# tick-box-1591A-mk-3_0.net
KiCad netlist of a schematic drawn in EAGLE
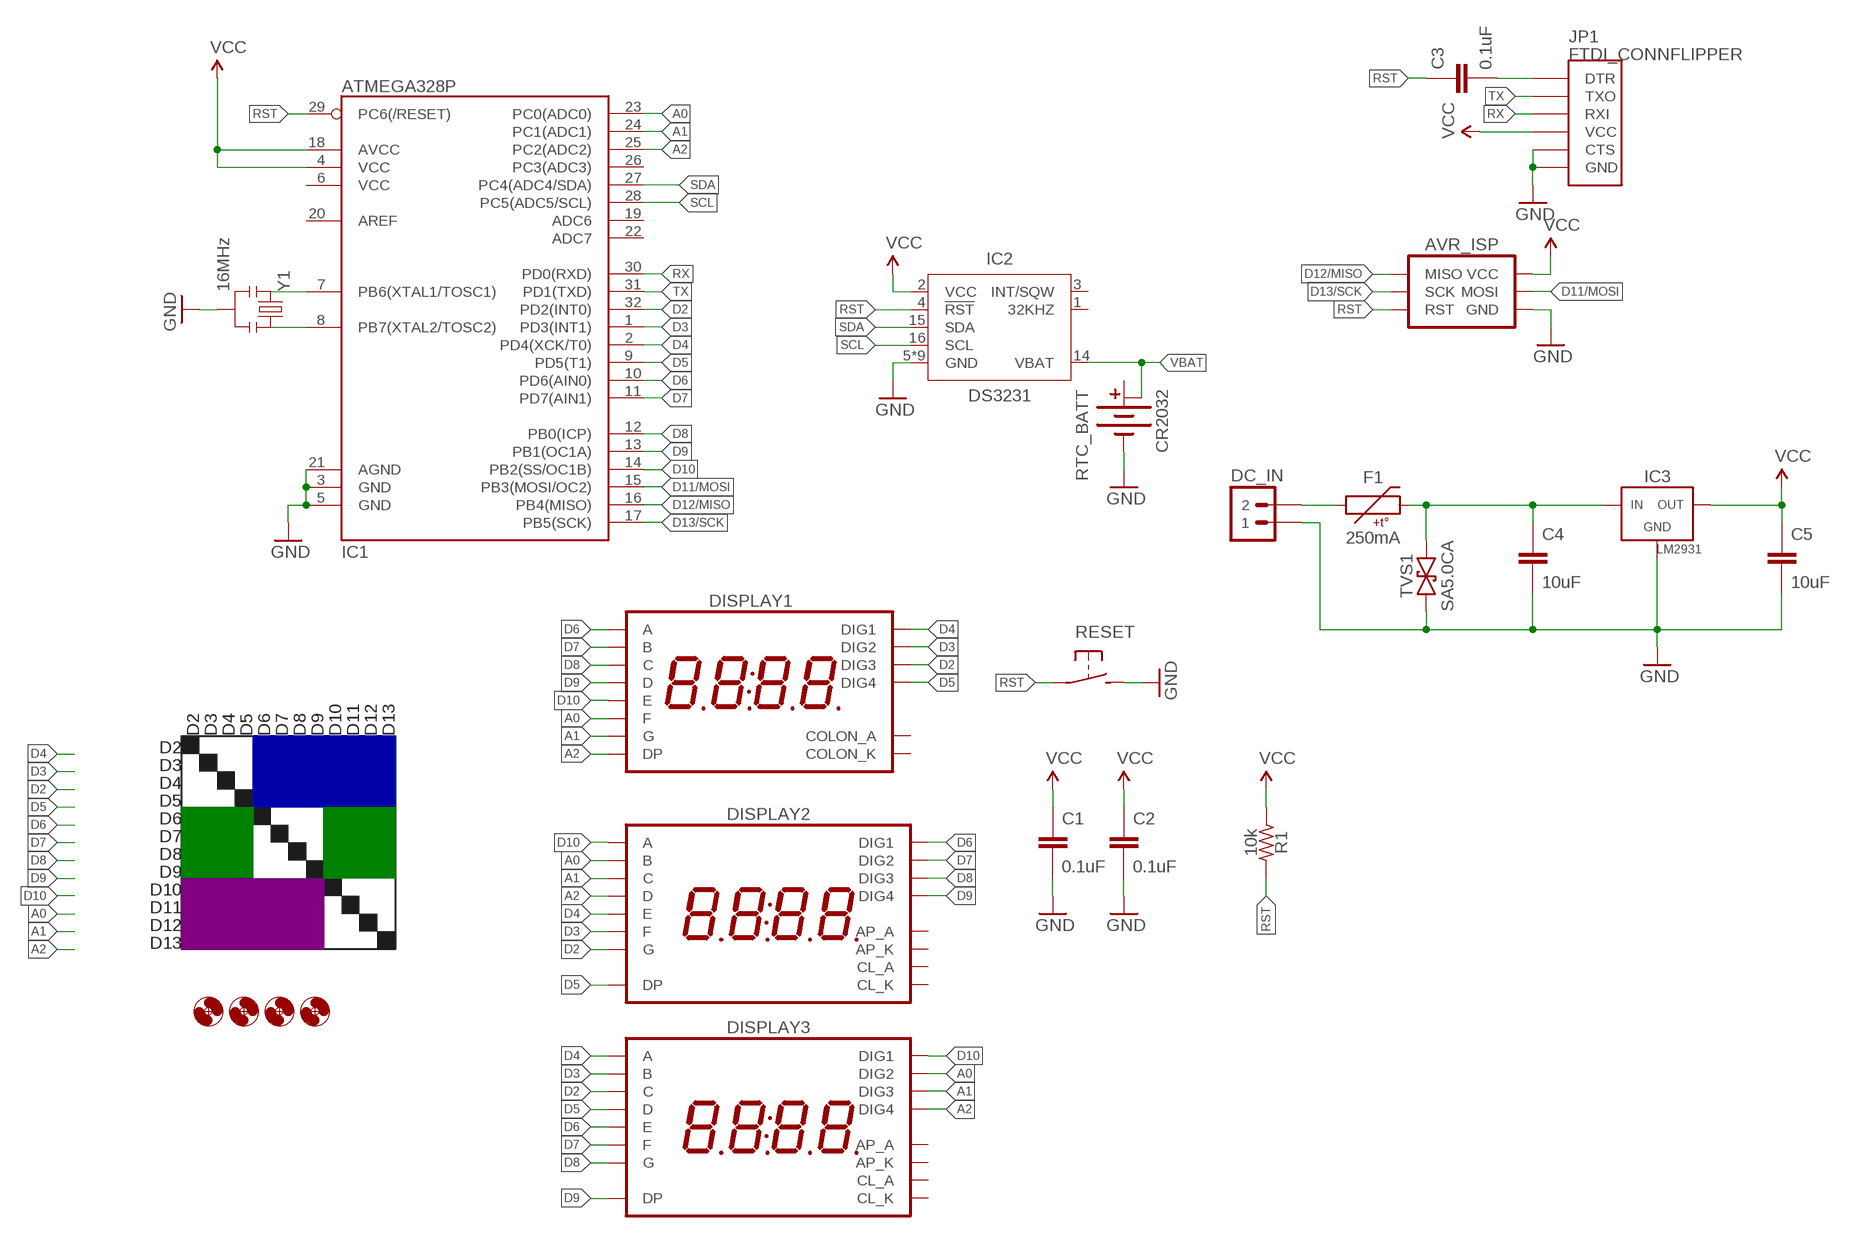
[diagram p0: schematic, sheet 1]

(export (version "E")
  (design (tool "Eeschema 10.0.6"))
  (components
    (comp (ref "AVR_ISP")
      (value "AVR_SPI_PRG_6PTH")
      (footprint "eagle-import:2X3")
      (libsource (lib "eagle-import") (part "AVR_SPI_PRG_6PTH"))
    )
    (comp (ref "C1")
      (value "0.1uF")
      (footprint "eagle-import:C0603")
      (libsource (lib "eagle-import") (part "CAPACITOR-CERAMICC0603"))
    )
    (comp (ref "C2")
      (value "0.1uF")
      (footprint "eagle-import:C0603")
      (libsource (lib "eagle-import") (part "CAPACITOR-CERAMICC0603"))
    )
    (comp (ref "C3")
      (value "0.1uF")
      (footprint "eagle-import:C0603")
      (libsource (lib "eagle-import") (part "CAPACITOR-CERAMICC0603"))
    )
    (comp (ref "C4")
      (value "10uF")
      (footprint "eagle-import:C1206")
      (libsource (lib "eagle-import") (part "CAPACITOR-CERAMICC1206"))
    )
    (comp (ref "C5")
      (value "10uF")
      (footprint "eagle-import:C1206")
      (libsource (lib "eagle-import") (part "CAPACITOR-CERAMICC1206"))
    )
    (comp (ref "DC_IN")
      (value "M02PTH")
      (footprint "eagle-import:1X02")
      (libsource (lib "eagle-import") (part "M02PTH"))
    )
    (comp (ref "DISPLAY1")
      (value "7SEG_4DIGIT_COLON14.2MM-CC-NS")
      (footprint "eagle-import:7SEG_4DIG_NS")
      (libsource (lib "eagle-import") (part "7SEG_4DIGIT_COLON14.2MM-CC-NS"))
    )
    (comp (ref "DISPLAY2")
      (value "7SEG_4DIGIT_COLON_APOS")
      (footprint "eagle-import:7SEG_4DIG_10MM")
      (libsource (lib "eagle-import") (part "7SEG_4DIGIT_COLON_APOS"))
    )
    (comp (ref "DISPLAY3")
      (value "7SEG_4DIGIT_COLON_APOS")
      (footprint "eagle-import:7SEG_4DIG_10MM")
      (libsource (lib "eagle-import") (part "7SEG_4DIGIT_COLON_APOS"))
    )
    (comp (ref "F1")
      (value "250mA")
      (footprint "eagle-import:PTC-1206")
      (libsource (lib "eagle-import") (part "PTCSMD"))
    )
    (comp (ref "H1")
      (value "HOLE#2")
      (footprint "eagle-import:HOLE-#2")
      (libsource (lib "eagle-import") (part "HOLE#2"))
    )
    (comp (ref "H2")
      (value "HOLE#2")
      (footprint "eagle-import:HOLE-#2")
      (libsource (lib "eagle-import") (part "HOLE#2"))
    )
    (comp (ref "H3")
      (value "HOLE#2")
      (footprint "eagle-import:HOLE-#2")
      (libsource (lib "eagle-import") (part "HOLE#2"))
    )
    (comp (ref "H4")
      (value "HOLE#2")
      (footprint "eagle-import:HOLE-#2")
      (libsource (lib "eagle-import") (part "HOLE#2"))
    )
    (comp (ref "IC1")
      (value "ATMEGA328P")
      (footprint "eagle-import:TQFP32-08")
      (libsource (lib "eagle-import") (part "ATMEGA328_SMT"))
    )
    (comp (ref "IC2")
      (value "DS3231")
      (footprint "eagle-import:SO16W")
      (libsource (lib "eagle-import") (part "DS3231"))
    )
    (comp (ref "IC3")
      (value "LM2931")
      (footprint "eagle-import:SO08")
      (libsource (lib "eagle-import") (part "LM2931-FIXED"))
    )
    (comp (ref "JP1")
      (value "FTDI_CONNFLIPPER")
      (footprint "eagle-import:FTDI_CONN_FLIP")
      (libsource (lib "eagle-import") (part "FTDI_CONNFLIPPER"))
    )
    (comp (ref "R1")
      (value "10k")
      (footprint "eagle-import:R0603")
      (libsource (lib "eagle-import") (part "RESISTORR0603"))
    )
    (comp (ref "RESET")
      (value "SPST-NO-TACT3MM-PTH-SMALL-PADS")
      (footprint "eagle-import:DTS-3-SMALL-PADS")
      (libsource (lib "eagle-import") (part "SPST-NO-TACT3MM-PTH-SMALL-PADS"))
    )
    (comp (ref "RTC_BATT")
      (value "CR2032")
      (footprint "eagle-import:BATTCON_20MM_MINE")
      (libsource (lib "eagle-import") (part "BATTERY-COINCR2032_SMD"))
    )
    (comp (ref "TVS1")
      (value "SA5.0CA")
      (footprint "eagle-import:SMA-DIODE-TVS-BIDIR")
      (libsource (lib "eagle-import") (part "TVSSMA"))
    )
    (comp (ref "Y1")
      (value "16MHz")
      (footprint "eagle-import:CSTCE_V_RESONATOR")
      (libsource (lib "eagle-import") (part "RESONATORCSTCE_V"))
    )
  )
  (nets
    (net (code "1") (name "A0") (class "Default")
      (node (ref "DISPLAY1") (pin "P$12") (pinfunction "F_P$12") (pintype "passive"))
      (node (ref "DISPLAY2") (pin "16") (pinfunction "B_16") (pintype "passive"))
      (node (ref "DISPLAY3") (pin "2") (pinfunction "DIG2_2") (pintype "passive"))
      (node (ref "IC1") (pin "23") (pinfunction "PC0(ADC0)_23") (pintype "bidirectional"))
    )
    (net (code "2") (name "A1") (class "Default")
      (node (ref "DISPLAY1") (pin "P$5") (pinfunction "G_P$5") (pintype "passive"))
      (node (ref "DISPLAY2") (pin "13") (pinfunction "C_13") (pintype "passive"))
      (node (ref "DISPLAY3") (pin "6") (pinfunction "DIG3_6") (pintype "passive"))
      (node (ref "IC1") (pin "24") (pinfunction "PC1(ADC1)_24") (pintype "bidirectional"))
    )
    (net (code "3") (name "A2") (class "Default")
      (node (ref "DISPLAY1") (pin "P$3") (pinfunction "DP_P$3") (pintype "passive"))
      (node (ref "DISPLAY2") (pin "3") (pinfunction "D_3") (pintype "passive"))
      (node (ref "DISPLAY3") (pin "8") (pinfunction "DIG4_8") (pintype "passive"))
      (node (ref "IC1") (pin "25") (pinfunction "PC2(ADC2)_25") (pintype "bidirectional"))
    )
    (net (code "4") (name "D2") (class "Default")
      (node (ref "DISPLAY1") (pin "P$10") (pinfunction "DIG3_P$10") (pintype "passive"))
      (node (ref "DISPLAY2") (pin "15") (pinfunction "G_15") (pintype "passive"))
      (node (ref "DISPLAY3") (pin "13") (pinfunction "C_13") (pintype "passive"))
      (node (ref "IC1") (pin "32") (pinfunction "PD2(INT0)_32") (pintype "bidirectional"))
    )
    (net (code "5") (name "D3") (class "Default")
      (node (ref "DISPLAY1") (pin "P$11") (pinfunction "DIG2_P$11") (pintype "passive"))
      (node (ref "DISPLAY2") (pin "11") (pinfunction "F_11") (pintype "passive"))
      (node (ref "DISPLAY3") (pin "16") (pinfunction "B_16") (pintype "passive"))
      (node (ref "IC1") (pin "1") (pinfunction "PD3(INT1)_1") (pintype "bidirectional"))
    )
    (net (code "6") (name "D4") (class "Default")
      (node (ref "DISPLAY1") (pin "P$14") (pinfunction "DIG1_P$14") (pintype "passive"))
      (node (ref "DISPLAY2") (pin "5") (pinfunction "E_5") (pintype "passive"))
      (node (ref "DISPLAY3") (pin "14") (pinfunction "A_14") (pintype "passive"))
      (node (ref "IC1") (pin "2") (pinfunction "PD4(XCK/T0)_2") (pintype "bidirectional"))
    )
    (net (code "7") (name "D5") (class "Default")
      (node (ref "DISPLAY1") (pin "P$6") (pinfunction "DIG4_P$6") (pintype "passive"))
      (node (ref "DISPLAY2") (pin "7") (pinfunction "DP_7") (pintype "passive"))
      (node (ref "DISPLAY3") (pin "3") (pinfunction "D_3") (pintype "passive"))
      (node (ref "IC1") (pin "9") (pinfunction "PD5(T1)_9") (pintype "bidirectional"))
    )
    (net (code "8") (name "D6") (class "Default")
      (node (ref "DISPLAY1") (pin "P$13") (pinfunction "A_P$13") (pintype "passive"))
      (node (ref "DISPLAY2") (pin "1") (pinfunction "DIG1_1") (pintype "passive"))
      (node (ref "DISPLAY3") (pin "5") (pinfunction "E_5") (pintype "passive"))
      (node (ref "IC1") (pin "10") (pinfunction "PD6(AIN0)_10") (pintype "bidirectional"))
    )
    (net (code "9") (name "D7") (class "Default")
      (node (ref "DISPLAY1") (pin "P$9") (pinfunction "B_P$9") (pintype "passive"))
      (node (ref "DISPLAY2") (pin "2") (pinfunction "DIG2_2") (pintype "passive"))
      (node (ref "DISPLAY3") (pin "11") (pinfunction "F_11") (pintype "passive"))
      (node (ref "IC1") (pin "11") (pinfunction "PD7(AIN1)_11") (pintype "bidirectional"))
    )
    (net (code "10") (name "D8") (class "Default")
      (node (ref "DISPLAY1") (pin "P$4") (pinfunction "C_P$4") (pintype "passive"))
      (node (ref "DISPLAY2") (pin "6") (pinfunction "DIG3_6") (pintype "passive"))
      (node (ref "DISPLAY3") (pin "15") (pinfunction "G_15") (pintype "passive"))
      (node (ref "IC1") (pin "12") (pinfunction "PB0(ICP)_12") (pintype "bidirectional"))
    )
    (net (code "11") (name "D9") (class "Default")
      (node (ref "DISPLAY1") (pin "P$2") (pinfunction "D_P$2") (pintype "passive"))
      (node (ref "DISPLAY2") (pin "8") (pinfunction "DIG4_8") (pintype "passive"))
      (node (ref "DISPLAY3") (pin "7") (pinfunction "DP_7") (pintype "passive"))
      (node (ref "IC1") (pin "13") (pinfunction "PB1(OC1A)_13") (pintype "bidirectional"))
    )
    (net (code "12") (name "D10") (class "Default")
      (node (ref "DISPLAY1") (pin "P$1") (pinfunction "E_P$1") (pintype "passive"))
      (node (ref "DISPLAY2") (pin "14") (pinfunction "A_14") (pintype "passive"))
      (node (ref "DISPLAY3") (pin "1") (pinfunction "DIG1_1") (pintype "passive"))
      (node (ref "IC1") (pin "14") (pinfunction "PB2(SS/OC1B)_14") (pintype "bidirectional"))
    )
    (net (code "13") (name "D11{slash}MOSI") (class "Default")
      (node (ref "AVR_ISP") (pin "4") (pinfunction "MOSI_4") (pintype "passive"))
      (node (ref "IC1") (pin "15") (pinfunction "PB3(MOSI/OC2)_15") (pintype "bidirectional"))
    )
    (net (code "14") (name "D12{slash}MISO") (class "Default")
      (node (ref "AVR_ISP") (pin "1") (pinfunction "MISO_1") (pintype "passive"))
      (node (ref "IC1") (pin "16") (pinfunction "PB4(MISO)_16") (pintype "bidirectional"))
    )
    (net (code "15") (name "D13{slash}SCK") (class "Default")
      (node (ref "AVR_ISP") (pin "3") (pinfunction "SCK_3") (pintype "passive"))
      (node (ref "IC1") (pin "17") (pinfunction "PB5(SCK)_17") (pintype "bidirectional"))
    )
    (net (code "16") (name "GND") (class "Default")
      (node (ref "AVR_ISP") (pin "6") (pinfunction "GND_6") (pintype "passive"))
      (node (ref "C1") (pin "2") (pinfunction "2_2") (pintype "passive"))
      (node (ref "C2") (pin "2") (pinfunction "2_2") (pintype "passive"))
      (node (ref "C4") (pin "2") (pinfunction "2_2") (pintype "passive"))
      (node (ref "C5") (pin "2") (pinfunction "2_2") (pintype "passive"))
      (node (ref "DC_IN") (pin "1") (pinfunction "1_1") (pintype "passive"))
      (node (ref "IC1") (pin "21") (pinfunction "AGND_21") (pintype "bidirectional"))
      (node (ref "IC1") (pin "3") (pinfunction "GND_3") (pintype "bidirectional"))
      (node (ref "IC1") (pin "5") (pinfunction "GND_5") (pintype "bidirectional"))
      (node (ref "IC2") (pin "10") (pinfunction "GND_10") (pintype "bidirectional"))
      (node (ref "IC2") (pin "11") (pinfunction "GND_11") (pintype "bidirectional"))
      (node (ref "IC2") (pin "12") (pinfunction "GND_12") (pintype "bidirectional"))
      (node (ref "IC2") (pin "13") (pinfunction "GND_13") (pintype "bidirectional"))
      (node (ref "IC2") (pin "5") (pinfunction "GND_5") (pintype "bidirectional"))
      (node (ref "IC2") (pin "6") (pinfunction "GND_6") (pintype "bidirectional"))
      (node (ref "IC2") (pin "7") (pinfunction "GND_7") (pintype "bidirectional"))
      (node (ref "IC2") (pin "8") (pinfunction "GND_8") (pintype "bidirectional"))
      (node (ref "IC2") (pin "9") (pinfunction "GND_9") (pintype "bidirectional"))
      (node (ref "IC3") (pin "2") (pinfunction "GND_2") (pintype "bidirectional"))
      (node (ref "IC3") (pin "3") (pinfunction "GND_3") (pintype "bidirectional"))
      (node (ref "IC3") (pin "4") (pinfunction "GND_4") (pintype "bidirectional"))
      (node (ref "IC3") (pin "5") (pinfunction "GND_5") (pintype "bidirectional"))
      (node (ref "IC3") (pin "6") (pinfunction "GND_6") (pintype "bidirectional"))
      (node (ref "IC3") (pin "7") (pinfunction "GND_7") (pintype "bidirectional"))
      (node (ref "JP1") (pin "CTS") (pinfunction "CTS_CTS") (pintype "bidirectional"))
      (node (ref "JP1") (pin "GND") (pinfunction "GND_GND") (pintype "bidirectional"))
      (node (ref "RESET") (pin "2") (pinfunction "2_2") (pintype "passive"))
      (node (ref "RTC_BATT") (pin "BOTTOM") (pinfunction "-_BOTTOM") (pintype "bidirectional"))
      (node (ref "TVS1") (pin "1") (pinfunction "1_1") (pintype "passive"))
      (node (ref "Y1") (pin "2") (pinfunction "2_2") (pintype "passive"))
    )
    (net (code "17") (name "Net-(C3-Pad2)") (class "Default")
      (node (ref "C3") (pin "2") (pinfunction "2_2") (pintype "passive"))
      (node (ref "JP1") (pin "DTR") (pinfunction "DTR_DTR") (pintype "bidirectional"))
    )
    (net (code "18") (name "Net-(DC_IN-Pad2)") (class "Default")
      (node (ref "DC_IN") (pin "2") (pinfunction "2_2") (pintype "passive"))
      (node (ref "F1") (pin "1") (pinfunction "1_1") (pintype "passive"))
    )
    (net (code "19") (name "Net-(IC1-PB6(XTAL1{slash}TOSC1))") (class "Default")
      (node (ref "IC1") (pin "7") (pinfunction "PB6(XTAL1/TOSC1)_7") (pintype "bidirectional"))
      (node (ref "Y1") (pin "3") (pinfunction "3_3") (pintype "passive"))
    )
    (net (code "20") (name "Net-(IC1-PB7(XTAL2{slash}TOSC2))") (class "Default")
      (node (ref "IC1") (pin "8") (pinfunction "PB7(XTAL2/TOSC2)_8") (pintype "bidirectional"))
      (node (ref "Y1") (pin "1") (pinfunction "1_1") (pintype "passive"))
    )
    (net (code "21") (name "Net-(IC3-IN)") (class "Default")
      (node (ref "C4") (pin "1") (pinfunction "1_1") (pintype "passive"))
      (node (ref "F1") (pin "2") (pinfunction "2_2") (pintype "passive"))
      (node (ref "IC3") (pin "8") (pinfunction "IN_8") (pintype "bidirectional"))
      (node (ref "TVS1") (pin "2") (pinfunction "2_2") (pintype "passive"))
    )
    (net (code "22") (name "RST") (class "Default")
      (node (ref "AVR_ISP") (pin "5") (pinfunction "RST_5") (pintype "passive"))
      (node (ref "C3") (pin "1") (pinfunction "1_1") (pintype "passive"))
      (node (ref "IC1") (pin "29") (pinfunction "PC6(/RESET)_29") (pintype "bidirectional"))
      (node (ref "IC2") (pin "4") (pinfunction "~{RST}_4") (pintype "bidirectional"))
      (node (ref "R1") (pin "2") (pinfunction "2_2") (pintype "passive"))
      (node (ref "RESET") (pin "1") (pinfunction "1_1") (pintype "passive"))
    )
    (net (code "23") (name "RX") (class "Default")
      (node (ref "IC1") (pin "30") (pinfunction "PD0(RXD)_30") (pintype "bidirectional"))
      (node (ref "JP1") (pin "RXI") (pinfunction "RXI_RXI") (pintype "bidirectional"))
    )
    (net (code "24") (name "SCL") (class "Default")
      (node (ref "IC1") (pin "28") (pinfunction "PC5(ADC5/SCL)_28") (pintype "bidirectional"))
      (node (ref "IC2") (pin "16") (pinfunction "SCL_16") (pintype "bidirectional"))
    )
    (net (code "25") (name "SDA") (class "Default")
      (node (ref "IC1") (pin "27") (pinfunction "PC4(ADC4/SDA)_27") (pintype "bidirectional"))
      (node (ref "IC2") (pin "15") (pinfunction "SDA_15") (pintype "bidirectional"))
    )
    (net (code "26") (name "TX") (class "Default")
      (node (ref "IC1") (pin "31") (pinfunction "PD1(TXD)_31") (pintype "bidirectional"))
      (node (ref "JP1") (pin "TXO") (pinfunction "TXO_TXO") (pintype "bidirectional"))
    )
    (net (code "27") (name "VBAT") (class "Default")
      (node (ref "IC2") (pin "14") (pinfunction "VBAT_14") (pintype "bidirectional"))
      (node (ref "RTC_BATT") (pin "TOP@2") (pinfunction "+1_TOP@2") (pintype "bidirectional"))
    )
    (net (code "28") (name "VCC") (class "Default")
      (node (ref "AVR_ISP") (pin "2") (pinfunction "VCC_2") (pintype "passive"))
      (node (ref "C1") (pin "1") (pinfunction "1_1") (pintype "passive"))
      (node (ref "C2") (pin "1") (pinfunction "1_1") (pintype "passive"))
      (node (ref "C5") (pin "1") (pinfunction "1_1") (pintype "passive"))
      (node (ref "IC1") (pin "18") (pinfunction "AVCC_18") (pintype "bidirectional"))
      (node (ref "IC1") (pin "4") (pinfunction "VCC_4") (pintype "bidirectional"))
      (node (ref "IC2") (pin "2") (pinfunction "VCC_2") (pintype "bidirectional"))
      (node (ref "IC3") (pin "1") (pinfunction "OUT_1") (pintype "bidirectional"))
      (node (ref "JP1") (pin "VCC") (pinfunction "VCC_VCC") (pintype "bidirectional"))
      (node (ref "R1") (pin "1") (pinfunction "1_1") (pintype "passive"))
    )
    (net (code "29") (name "unconnected-(DISPLAY1-COLON_A-PadP$8)") (class "Default")
      (node (ref "DISPLAY1") (pin "P$8") (pinfunction "COLON_A_P$8") (pintype "passive"))
    )
    (net (code "30") (name "unconnected-(DISPLAY1-COLON_K-PadP$7)") (class "Default")
      (node (ref "DISPLAY1") (pin "P$7") (pinfunction "COLON_K_P$7") (pintype "passive"))
    )
    (net (code "31") (name "unconnected-(DISPLAY2-AP_A-Pad10)") (class "Default")
      (node (ref "DISPLAY2") (pin "10") (pinfunction "AP_A_10") (pintype "bidirectional"))
    )
    (net (code "32") (name "unconnected-(DISPLAY2-AP_K-Pad9)") (class "Default")
      (node (ref "DISPLAY2") (pin "9") (pinfunction "AP_K_9") (pintype "bidirectional"))
    )
    (net (code "33") (name "unconnected-(DISPLAY2-CL_A-Pad4)") (class "Default")
      (node (ref "DISPLAY2") (pin "4") (pinfunction "CL_A_4") (pintype "passive"))
    )
    (net (code "34") (name "unconnected-(DISPLAY2-CL_K-Pad12)") (class "Default")
      (node (ref "DISPLAY2") (pin "12") (pinfunction "CL_K_12") (pintype "passive"))
    )
    (net (code "35") (name "unconnected-(DISPLAY3-AP_A-Pad10)") (class "Default")
      (node (ref "DISPLAY3") (pin "10") (pinfunction "AP_A_10") (pintype "bidirectional"))
    )
    (net (code "36") (name "unconnected-(DISPLAY3-AP_K-Pad9)") (class "Default")
      (node (ref "DISPLAY3") (pin "9") (pinfunction "AP_K_9") (pintype "bidirectional"))
    )
    (net (code "37") (name "unconnected-(DISPLAY3-CL_A-Pad4)") (class "Default")
      (node (ref "DISPLAY3") (pin "4") (pinfunction "CL_A_4") (pintype "passive"))
    )
    (net (code "38") (name "unconnected-(DISPLAY3-CL_K-Pad12)") (class "Default")
      (node (ref "DISPLAY3") (pin "12") (pinfunction "CL_K_12") (pintype "passive"))
    )
    (net (code "39") (name "unconnected-(IC1-ADC6-Pad19)") (class "Default")
      (node (ref "IC1") (pin "19") (pinfunction "ADC6_19") (pintype "bidirectional"))
    )
    (net (code "40") (name "unconnected-(IC1-ADC7-Pad22)") (class "Default")
      (node (ref "IC1") (pin "22") (pinfunction "ADC7_22") (pintype "bidirectional"))
    )
    (net (code "41") (name "unconnected-(IC1-AREF-Pad20)") (class "Default")
      (node (ref "IC1") (pin "20") (pinfunction "AREF_20") (pintype "bidirectional"))
    )
    (net (code "42") (name "unconnected-(IC1-PC3(ADC3)-Pad26)") (class "Default")
      (node (ref "IC1") (pin "26") (pinfunction "PC3(ADC3)_26") (pintype "bidirectional"))
    )
    (net (code "43") (name "unconnected-(IC1-VCC-Pad6)") (class "Default")
      (node (ref "IC1") (pin "6") (pinfunction "VCC_6") (pintype "bidirectional"))
    )
    (net (code "44") (name "unconnected-(IC2-32KHZ-Pad1)") (class "Default")
      (node (ref "IC2") (pin "1") (pinfunction "32KHZ_1") (pintype "bidirectional"))
    )
    (net (code "45") (name "unconnected-(IC2-INT{slash}SQW-Pad3)") (class "Default")
      (node (ref "IC2") (pin "3") (pinfunction "INT/SQW_3") (pintype "bidirectional"))
    )
    (net (code "46") (name "unconnected-(RTC_BATT-+-PadTOP@1)") (class "Default")
      (node (ref "RTC_BATT") (pin "TOP@1") (pinfunction "+_TOP@1") (pintype "bidirectional"))
    )
  )
)
